# NavButtons.net
KiCad netlist of a schematic drawn in EAGLE
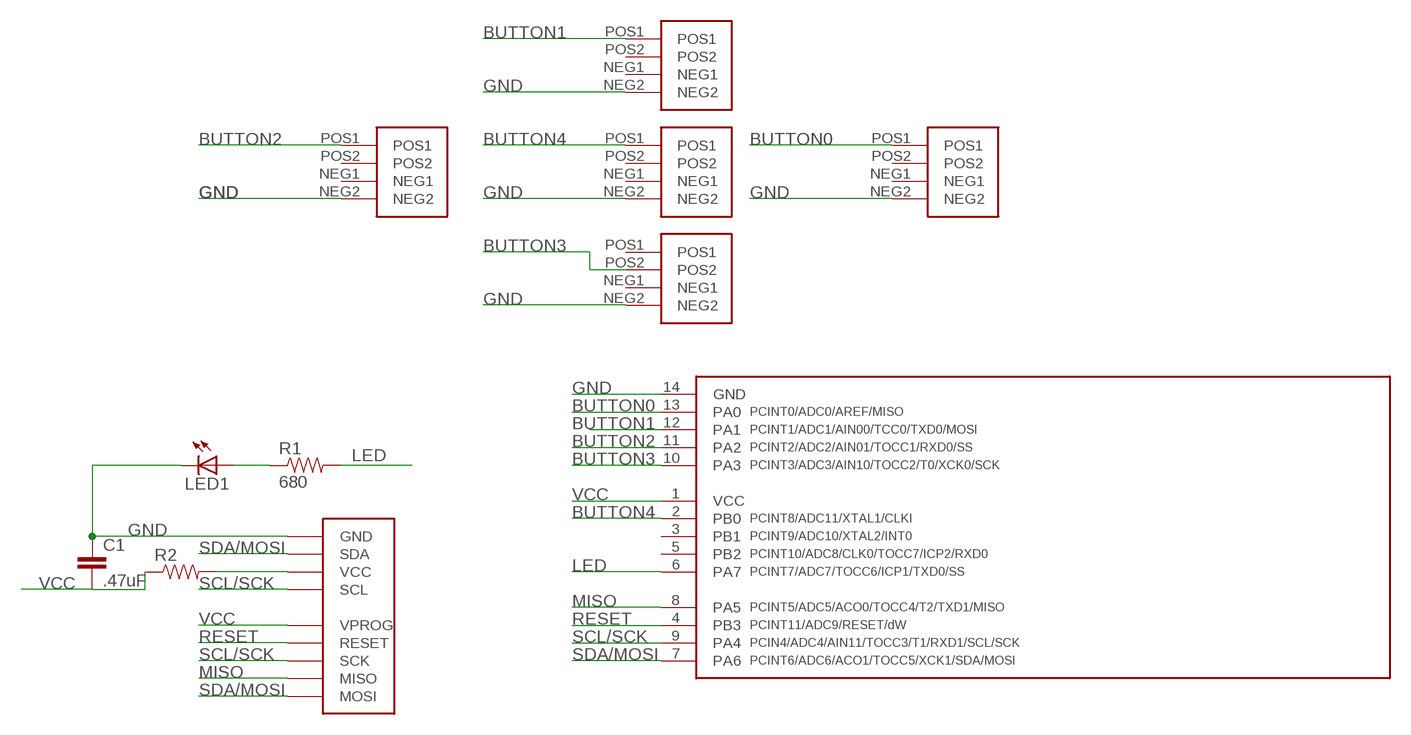
[diagram p0: schematic, sheet 1]

(export (version "E")
  (design (tool "Eeschema 10.0.6"))
  (components
    (comp (ref "B1")
      (value "TACT-SWITCH")
      (footprint "eagle-import:MJTP1138")
      (libsource (lib "eagle-import") (part "TACT-SWITCH"))
    )
    (comp (ref "B3")
      (value "TACT-SWITCH")
      (footprint "eagle-import:MJTP1138")
      (libsource (lib "eagle-import") (part "TACT-SWITCH"))
    )
    (comp (ref "B4")
      (value "TACT-SWITCH")
      (footprint "eagle-import:MJTP1138")
      (libsource (lib "eagle-import") (part "TACT-SWITCH"))
    )
    (comp (ref "B5")
      (value "TACT-SWITCH")
      (footprint "eagle-import:MJTP1138")
      (libsource (lib "eagle-import") (part "TACT-SWITCH"))
    )
    (comp (ref "B7")
      (value "TACT-SWITCH")
      (footprint "eagle-import:MJTP1138")
      (libsource (lib "eagle-import") (part "TACT-SWITCH"))
    )
    (comp (ref "C1")
      (value ".47uF")
      (footprint "eagle-import:0805")
      (libsource (lib "eagle-import") (part "CAP0805"))
    )
    (comp (ref "LED1")
      (value "LEDCHIP-LED0805")
      (footprint "eagle-import:CHIP-LED0805")
      (libsource (lib "eagle-import") (part "LEDCHIP-LED0805"))
    )
    (comp (ref "R1")
      (value "680")
      (footprint "eagle-import:0805")
      (libsource (lib "eagle-import") (part "RESISTOR0805-RES"))
    )
    (comp (ref "R2")
      (value "RESISTOR0805-RES")
      (footprint "eagle-import:0805")
      (libsource (lib "eagle-import") (part "SparkFun-Resistors_RESISTOR0805-RES"))
    )
    (comp (ref "U$1")
      (value "TINY841")
      (footprint "eagle-import:SOIC14")
      (libsource (lib "eagle-import") (part "TINY841"))
    )
    (comp (ref "U$2")
      (value "FOOTPRINTFOOTPRINT-2")
      (footprint "eagle-import:FOOTPRINT2")
      (libsource (lib "eagle-import") (part "FOOTPRINTFOOTPRINT-2"))
    )
  )
  (nets
    (net (code "1") (name "/BUTTON0") (class "Default")
      (node (ref "B5") (pin "POS1") (pinfunction "POS1_POS1") (pintype "bidirectional"))
      (node (ref "U$1") (pin "13") (pinfunction "PA0_13") (pintype "bidirectional"))
    )
    (net (code "2") (name "/BUTTON1") (class "Default")
      (node (ref "B1") (pin "POS1") (pinfunction "POS1_POS1") (pintype "bidirectional"))
      (node (ref "U$1") (pin "12") (pinfunction "PA1_12") (pintype "bidirectional"))
    )
    (net (code "3") (name "/BUTTON2") (class "Default")
      (node (ref "B3") (pin "POS1") (pinfunction "POS1_POS1") (pintype "bidirectional"))
      (node (ref "U$1") (pin "11") (pinfunction "PA2_11") (pintype "bidirectional"))
    )
    (net (code "4") (name "/BUTTON3") (class "Default")
      (node (ref "B7") (pin "POS2") (pinfunction "POS2_POS2") (pintype "bidirectional"))
      (node (ref "U$1") (pin "10") (pinfunction "PA3_10") (pintype "bidirectional"))
    )
    (net (code "5") (name "/BUTTON4") (class "Default")
      (node (ref "B4") (pin "POS1") (pinfunction "POS1_POS1") (pintype "bidirectional"))
      (node (ref "U$1") (pin "2") (pinfunction "PB0_2") (pintype "bidirectional"))
    )
    (net (code "6") (name "/GND") (class "Default")
      (node (ref "B1") (pin "NEG2") (pinfunction "NEG2_NEG2") (pintype "bidirectional"))
      (node (ref "B3") (pin "NEG2") (pinfunction "NEG2_NEG2") (pintype "bidirectional"))
      (node (ref "B4") (pin "NEG2") (pinfunction "NEG2_NEG2") (pintype "bidirectional"))
      (node (ref "B5") (pin "NEG2") (pinfunction "NEG2_NEG2") (pintype "bidirectional"))
      (node (ref "B7") (pin "NEG2") (pinfunction "NEG2_NEG2") (pintype "bidirectional"))
      (node (ref "C1") (pin "1") (pinfunction "1_1") (pintype "passive"))
      (node (ref "LED1") (pin "C") (pinfunction "C_C") (pintype "passive"))
      (node (ref "U$1") (pin "14") (pinfunction "GND_14") (pintype "bidirectional"))
      (node (ref "U$2") (pin "BUS0") (pinfunction "GND_BUS0") (pintype "bidirectional"))
    )
    (net (code "7") (name "/LED") (class "Default")
      (node (ref "R1") (pin "2") (pinfunction "2_2") (pintype "passive"))
      (node (ref "U$1") (pin "6") (pinfunction "PA7_6") (pintype "bidirectional"))
    )
    (net (code "8") (name "/MISO") (class "Default")
      (node (ref "U$1") (pin "8") (pinfunction "PA5_8") (pintype "bidirectional"))
      (node (ref "U$2") (pin "PROG3") (pinfunction "MISO_PROG3") (pintype "bidirectional"))
    )
    (net (code "9") (name "/RESET") (class "Default")
      (node (ref "U$1") (pin "4") (pinfunction "PB3_4") (pintype "bidirectional"))
      (node (ref "U$2") (pin "PROG1") (pinfunction "RESET_PROG1") (pintype "bidirectional"))
    )
    (net (code "10") (name "/SCL{slash}SCK") (class "Default")
      (node (ref "U$1") (pin "9") (pinfunction "PA4_9") (pintype "bidirectional"))
      (node (ref "U$2") (pin "BUS3") (pinfunction "SCL_BUS3") (pintype "bidirectional"))
      (node (ref "U$2") (pin "PROG2") (pinfunction "SCK_PROG2") (pintype "bidirectional"))
    )
    (net (code "11") (name "/SDA{slash}MOSI") (class "Default")
      (node (ref "U$1") (pin "7") (pinfunction "PA6_7") (pintype "bidirectional"))
      (node (ref "U$2") (pin "BUS1") (pinfunction "SDA_BUS1") (pintype "bidirectional"))
      (node (ref "U$2") (pin "PROG4") (pinfunction "MOSI_PROG4") (pintype "bidirectional"))
    )
    (net (code "12") (name "/VCC") (class "Default")
      (node (ref "C1") (pin "2") (pinfunction "2_2") (pintype "passive"))
      (node (ref "R2") (pin "1") (pinfunction "1_1") (pintype "passive"))
      (node (ref "U$1") (pin "1") (pinfunction "VCC_1") (pintype "bidirectional"))
      (node (ref "U$2") (pin "PROG0") (pinfunction "VPROG_PROG0") (pintype "bidirectional"))
    )
    (net (code "13") (name "Net-(LED1-PadA)") (class "Default")
      (node (ref "LED1") (pin "A") (pinfunction "A_A") (pintype "passive"))
      (node (ref "R1") (pin "1") (pinfunction "1_1") (pintype "passive"))
    )
    (net (code "14") (name "Net-(U$2-VCC)") (class "Default")
      (node (ref "R2") (pin "2") (pinfunction "2_2") (pintype "passive"))
      (node (ref "U$2") (pin "BUS2") (pinfunction "VCC_BUS2") (pintype "bidirectional"))
    )
    (net (code "15") (name "unconnected-(B1-PadNEG1)") (class "Default")
      (node (ref "B1") (pin "NEG1") (pinfunction "NEG1_NEG1") (pintype "bidirectional"))
    )
    (net (code "16") (name "unconnected-(B1-PadPOS2)") (class "Default")
      (node (ref "B1") (pin "POS2") (pinfunction "POS2_POS2") (pintype "bidirectional"))
    )
    (net (code "17") (name "unconnected-(B3-PadNEG1)") (class "Default")
      (node (ref "B3") (pin "NEG1") (pinfunction "NEG1_NEG1") (pintype "bidirectional"))
    )
    (net (code "18") (name "unconnected-(B3-PadPOS2)") (class "Default")
      (node (ref "B3") (pin "POS2") (pinfunction "POS2_POS2") (pintype "bidirectional"))
    )
    (net (code "19") (name "unconnected-(B4-PadNEG1)") (class "Default")
      (node (ref "B4") (pin "NEG1") (pinfunction "NEG1_NEG1") (pintype "bidirectional"))
    )
    (net (code "20") (name "unconnected-(B4-PadPOS2)") (class "Default")
      (node (ref "B4") (pin "POS2") (pinfunction "POS2_POS2") (pintype "bidirectional"))
    )
    (net (code "21") (name "unconnected-(B5-PadNEG1)") (class "Default")
      (node (ref "B5") (pin "NEG1") (pinfunction "NEG1_NEG1") (pintype "bidirectional"))
    )
    (net (code "22") (name "unconnected-(B5-PadPOS2)") (class "Default")
      (node (ref "B5") (pin "POS2") (pinfunction "POS2_POS2") (pintype "bidirectional"))
    )
    (net (code "23") (name "unconnected-(B7-PadNEG1)") (class "Default")
      (node (ref "B7") (pin "NEG1") (pinfunction "NEG1_NEG1") (pintype "bidirectional"))
    )
    (net (code "24") (name "unconnected-(B7-PadPOS1)") (class "Default")
      (node (ref "B7") (pin "POS1") (pinfunction "POS1_POS1") (pintype "bidirectional"))
    )
    (net (code "25") (name "unconnected-(U$1-PB1-Pad3)") (class "Default")
      (node (ref "U$1") (pin "3") (pinfunction "PB1_3") (pintype "bidirectional"))
    )
    (net (code "26") (name "unconnected-(U$1-PB2-Pad5)") (class "Default")
      (node (ref "U$1") (pin "5") (pinfunction "PB2_5") (pintype "bidirectional"))
    )
  )
)
